# LifterPCB_v9.net
KiCad netlist of a schematic drawn in EAGLE
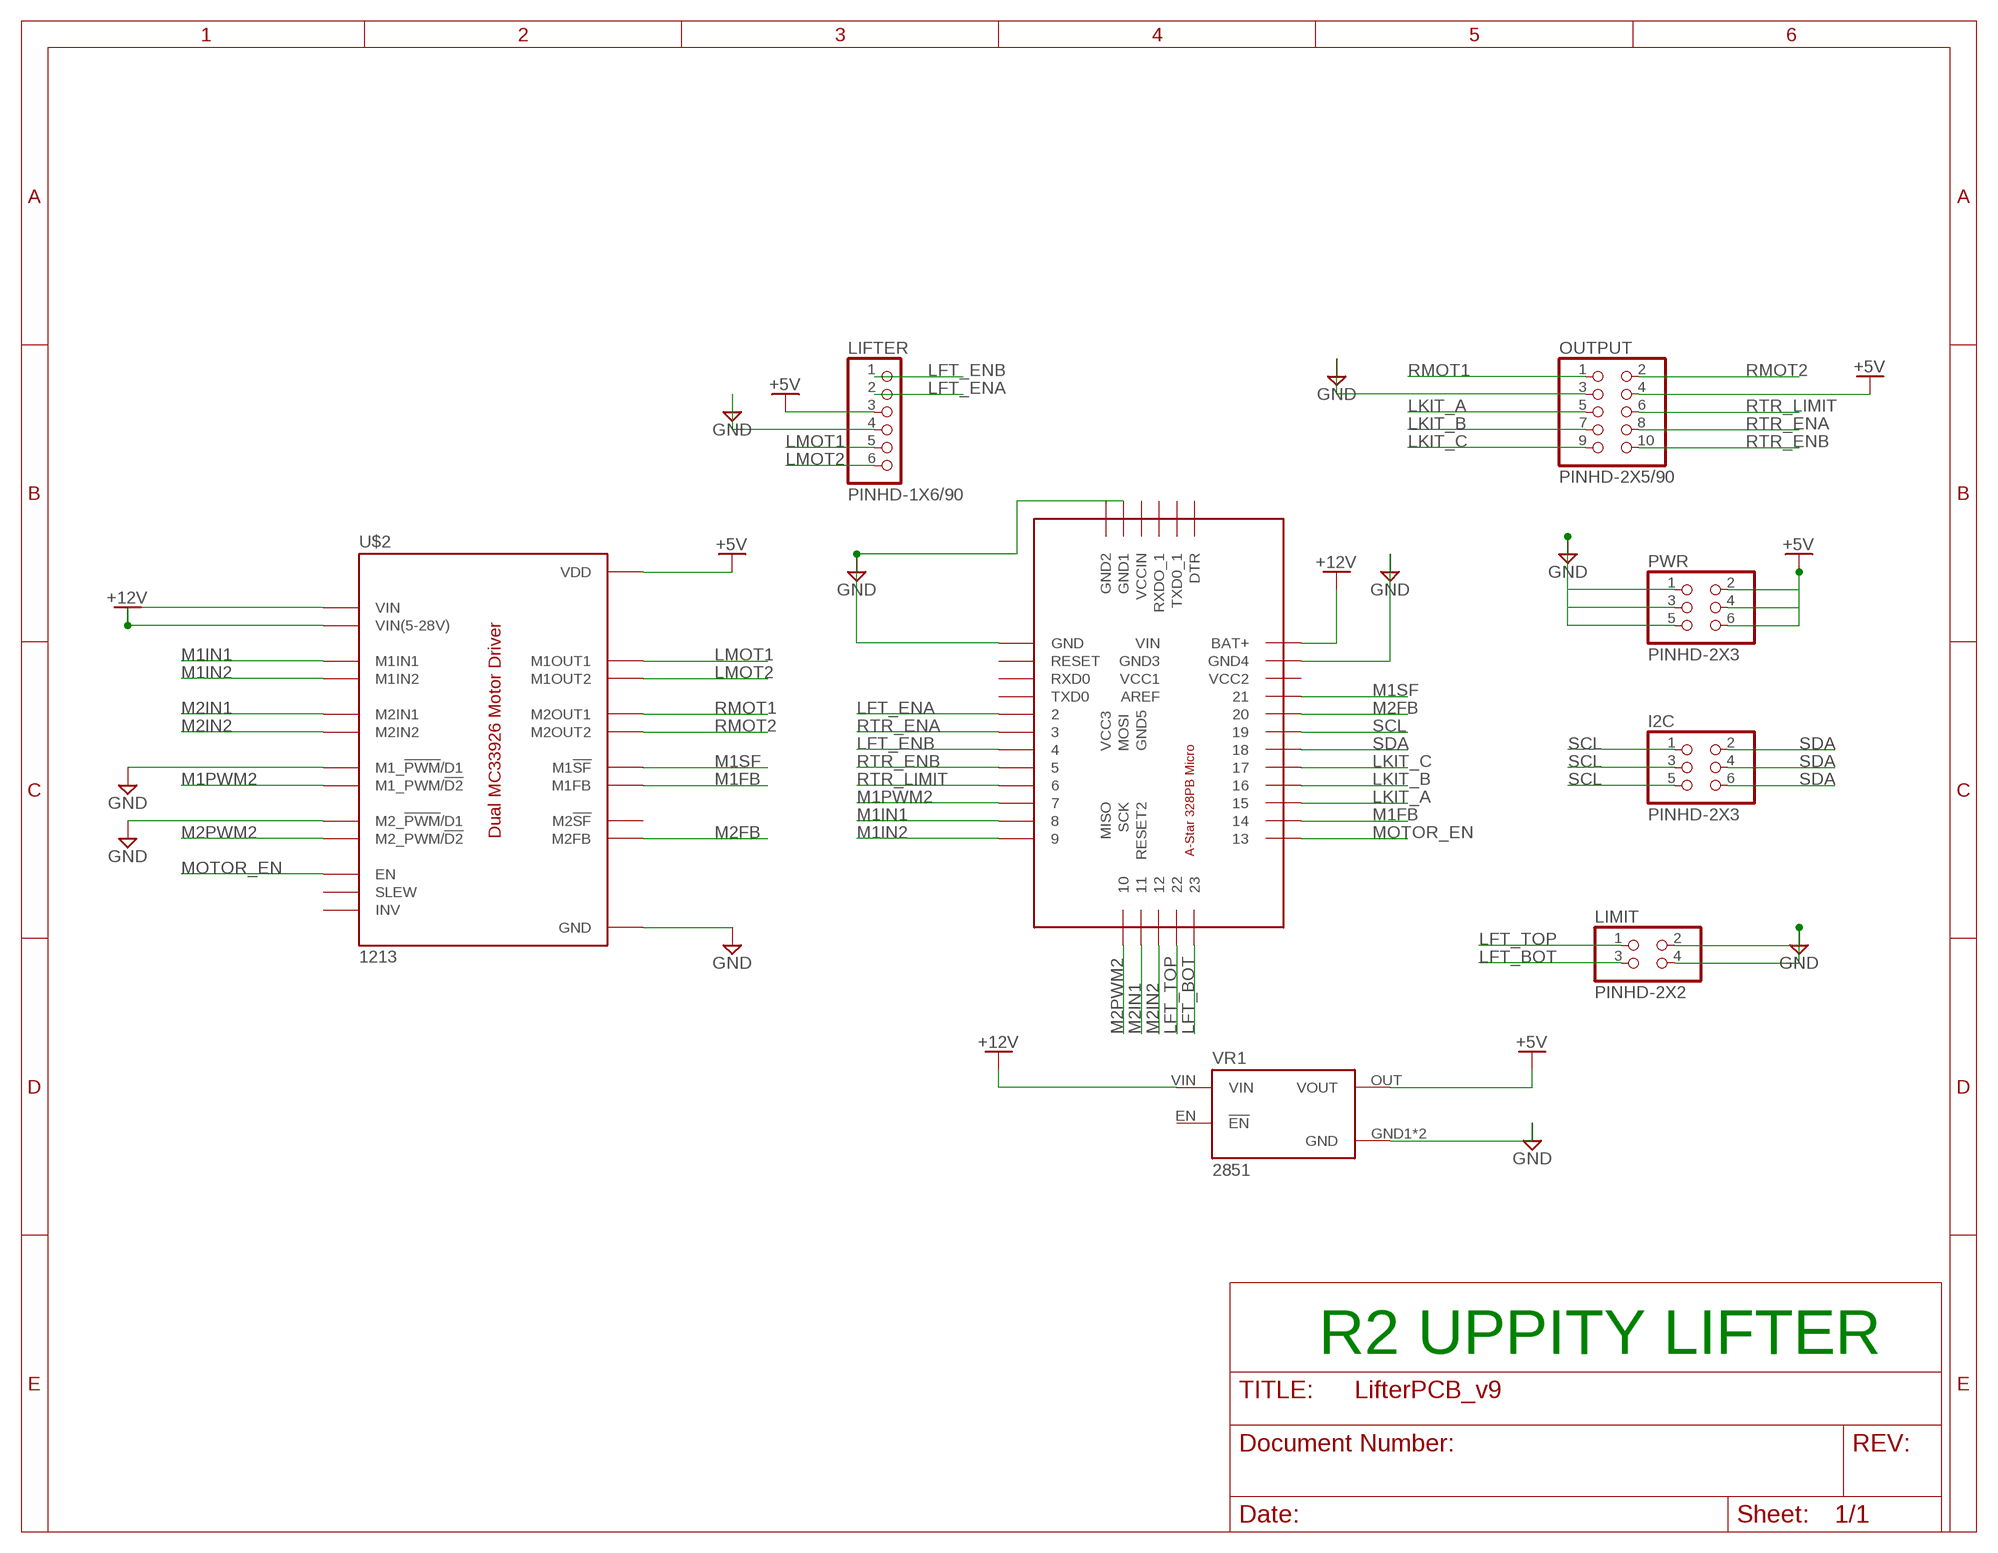
[diagram p0: schematic, sheet 1]

(export (version "E")
  (design (tool "Eeschema 10.0.6"))
  (components
    (comp (ref "I2C")
      (value "PINHD-2X3")
      (footprint "eagle-import:2X03")
      (libsource (lib "eagle-import") (part "PINHD-2X3"))
    )
    (comp (ref "LIFTER")
      (value "PINHD-1X6/90")
      (footprint "eagle-import:1X06_90")
      (libsource (lib "eagle-import") (part "PINHD-1X6/90"))
    )
    (comp (ref "LIMIT")
      (value "PINHD-2X2")
      (footprint "eagle-import:2X02")
      (libsource (lib "eagle-import") (part "PINHD-2X2"))
    )
    (comp (ref "OUTPUT")
      (value "PINHD-2X5/90")
      (footprint "eagle-import:2X05_90")
      (libsource (lib "eagle-import") (part "PINHD-2X5/90"))
    )
    (comp (ref "PWR")
      (value "PINHD-2X3")
      (footprint "eagle-import:2X03")
      (libsource (lib "eagle-import") (part "PINHD-2X3"))
    )
    (comp (ref "U$1")
      (value "POLOLU3161")
      (footprint "eagle-import:POLOLU3161")
      (libsource (lib "eagle-import") (part "POLOLU3161"))
    )
    (comp (ref "U$2")
      (value "1213")
      (footprint "eagle-import:1213")
      (libsource (lib "eagle-import") (part "1213"))
    )
    (comp (ref "VR1")
      (value "2851")
      (footprint "eagle-import:VREG_2851")
      (fields (field (name "MF") "Pololu"))
      (libsource (lib "eagle-import") (part "2851"))
    )
  )
  (nets
    (net (code "1") (name "+5V") (class "Default")
      (node (ref "LIFTER") (pin "3") (pinfunction "3_3") (pintype "passive"))
      (node (ref "OUTPUT") (pin "4") (pinfunction "4_4") (pintype "passive"))
      (node (ref "PWR") (pin "2") (pinfunction "2_2") (pintype "passive"))
      (node (ref "PWR") (pin "4") (pinfunction "4_4") (pintype "passive"))
      (node (ref "PWR") (pin "6") (pinfunction "6_6") (pintype "passive"))
      (node (ref "U$2") (pin "VDD") (pinfunction "VDD_VDD") (pintype "power_in"))
      (node (ref "U$2") (pin "VDD$1") (pinfunction "VDD_VDD$1") (pintype "power_in"))
      (node (ref "U$2") (pin "VDD$2") (pinfunction "VDD_VDD$2") (pintype "power_in"))
      (node (ref "U$2") (pin "VDD$3") (pinfunction "VDD_VDD$3") (pintype "power_in"))
      (node (ref "U$2") (pin "VDD$4") (pinfunction "VDD_VDD$4") (pintype "power_in"))
      (node (ref "U$2") (pin "VDD$5") (pinfunction "VDD_VDD$5") (pintype "power_in"))
      (node (ref "VR1") (pin "OUT") (pinfunction "VOUT_OUT") (pintype "output"))
    )
    (net (code "2") (name "+12V") (class "Default")
      (node (ref "U$1") (pin "BAT+") (pinfunction "BAT+_BAT+") (pintype "input"))
      (node (ref "U$2") (pin "MVIN") (pinfunction "VIN(5-28V)_MVIN") (pintype "input"))
      (node (ref "U$2") (pin "VIN") (pinfunction "VIN_VIN") (pintype "input"))
      (node (ref "VR1") (pin "VIN") (pinfunction "VIN_VIN") (pintype "input"))
    )
    (net (code "3") (name "/LFT_BOT") (class "Default")
      (node (ref "LIMIT") (pin "3") (pinfunction "3_3") (pintype "passive"))
      (node (ref "U$1") (pin "23") (pinfunction "23_23") (pintype "input"))
    )
    (net (code "4") (name "/LFT_ENA") (class "Default")
      (node (ref "LIFTER") (pin "2") (pinfunction "2_2") (pintype "passive"))
      (node (ref "U$1") (pin "2") (pinfunction "2_2") (pintype "input"))
    )
    (net (code "5") (name "/LFT_ENB") (class "Default")
      (node (ref "LIFTER") (pin "1") (pinfunction "1_1") (pintype "passive"))
      (node (ref "U$1") (pin "4") (pinfunction "4_4") (pintype "input"))
    )
    (net (code "6") (name "/LFT_TOP") (class "Default")
      (node (ref "LIMIT") (pin "1") (pinfunction "1_1") (pintype "passive"))
      (node (ref "U$1") (pin "22") (pinfunction "22_22") (pintype "input"))
    )
    (net (code "7") (name "/LKIT_A") (class "Default")
      (node (ref "OUTPUT") (pin "5") (pinfunction "5_5") (pintype "passive"))
      (node (ref "U$1") (pin "15") (pinfunction "15_15") (pintype "input"))
    )
    (net (code "8") (name "/LKIT_B") (class "Default")
      (node (ref "OUTPUT") (pin "7") (pinfunction "7_7") (pintype "passive"))
      (node (ref "U$1") (pin "16") (pinfunction "16_16") (pintype "input"))
    )
    (net (code "9") (name "/LKIT_C") (class "Default")
      (node (ref "OUTPUT") (pin "9") (pinfunction "9_9") (pintype "passive"))
      (node (ref "U$1") (pin "17") (pinfunction "17_17") (pintype "input"))
    )
    (net (code "10") (name "/LMOT1") (class "Default")
      (node (ref "LIFTER") (pin "5") (pinfunction "5_5") (pintype "passive"))
      (node (ref "U$2") (pin "M1OUT1") (pinfunction "M1OUT1_M1OUT1") (pintype "output"))
    )
    (net (code "11") (name "/LMOT2") (class "Default")
      (node (ref "LIFTER") (pin "6") (pinfunction "6_6") (pintype "passive"))
      (node (ref "U$2") (pin "M1OUT2") (pinfunction "M1OUT2_M1OUT2") (pintype "output"))
    )
    (net (code "12") (name "/M1FB") (class "Default")
      (node (ref "U$1") (pin "14") (pinfunction "14_14") (pintype "input"))
      (node (ref "U$2") (pin "M1FB") (pinfunction "M1FB_M1FB") (pintype "output"))
    )
    (net (code "13") (name "/M1IN1") (class "Default")
      (node (ref "U$1") (pin "8") (pinfunction "8_8") (pintype "input"))
      (node (ref "U$2") (pin "M1IN1") (pinfunction "M1IN1_M1IN1") (pintype "input"))
    )
    (net (code "14") (name "/M1IN2") (class "Default")
      (node (ref "U$1") (pin "9") (pinfunction "9_9") (pintype "input"))
      (node (ref "U$2") (pin "M1IN2") (pinfunction "M1IN2_M1IN2") (pintype "input"))
    )
    (net (code "15") (name "/M1PWM2") (class "Default")
      (node (ref "U$1") (pin "7") (pinfunction "7_7") (pintype "input"))
      (node (ref "U$2") (pin "M1PWM2") (pinfunction "M1_PWM/~{D2}_M1PWM2") (pintype "input"))
    )
    (net (code "16") (name "/M1SF") (class "Default")
      (node (ref "U$1") (pin "21") (pinfunction "21_21") (pintype "input"))
      (node (ref "U$2") (pin "M1SF") (pinfunction "M1~{SF}_M1SF") (pintype "output"))
    )
    (net (code "17") (name "/M2FB") (class "Default")
      (node (ref "U$1") (pin "20") (pinfunction "20_20") (pintype "input"))
      (node (ref "U$2") (pin "M2FB") (pinfunction "M2FB_M2FB") (pintype "output"))
    )
    (net (code "18") (name "/M2IN1") (class "Default")
      (node (ref "U$1") (pin "11$1") (pinfunction "11_11$1") (pintype "input"))
      (node (ref "U$2") (pin "M2IN1") (pinfunction "M2IN1_M2IN1") (pintype "input"))
    )
    (net (code "19") (name "/M2IN2") (class "Default")
      (node (ref "U$1") (pin "12$1") (pinfunction "12_12$1") (pintype "input"))
      (node (ref "U$2") (pin "M2IN2") (pinfunction "M2IN2_M2IN2") (pintype "input"))
    )
    (net (code "20") (name "/M2PWM2") (class "Default")
      (node (ref "U$1") (pin "10") (pinfunction "10_10") (pintype "input"))
      (node (ref "U$2") (pin "M2PWM2") (pinfunction "M2_PWM/~{D2}_M2PWM2") (pintype "input"))
    )
    (net (code "21") (name "/MOTOR_EN") (class "Default")
      (node (ref "U$1") (pin "13$1") (pinfunction "13_13$1") (pintype "input"))
      (node (ref "U$2") (pin "EN") (pinfunction "EN_EN") (pintype "input"))
    )
    (net (code "22") (name "/RMOT1") (class "Default")
      (node (ref "OUTPUT") (pin "1") (pinfunction "1_1") (pintype "passive"))
      (node (ref "U$2") (pin "M2OUT1") (pinfunction "M2OUT1_M2OUT1") (pintype "output"))
    )
    (net (code "23") (name "/RMOT2") (class "Default")
      (node (ref "OUTPUT") (pin "2") (pinfunction "2_2") (pintype "passive"))
      (node (ref "U$2") (pin "M2OUT2") (pinfunction "M2OUT2_M2OUT2") (pintype "output"))
    )
    (net (code "24") (name "/RTR_ENA") (class "Default")
      (node (ref "OUTPUT") (pin "8") (pinfunction "8_8") (pintype "passive"))
      (node (ref "U$1") (pin "3") (pinfunction "3_3") (pintype "input"))
    )
    (net (code "25") (name "/RTR_ENB") (class "Default")
      (node (ref "OUTPUT") (pin "10") (pinfunction "10_10") (pintype "passive"))
      (node (ref "U$1") (pin "5") (pinfunction "5_5") (pintype "input"))
    )
    (net (code "26") (name "/RTR_LIMIT") (class "Default")
      (node (ref "OUTPUT") (pin "6") (pinfunction "6_6") (pintype "passive"))
      (node (ref "U$1") (pin "6") (pinfunction "6_6") (pintype "input"))
    )
    (net (code "27") (name "/SCL") (class "Default")
      (node (ref "I2C") (pin "1") (pinfunction "1_1") (pintype "passive"))
      (node (ref "I2C") (pin "3") (pinfunction "3_3") (pintype "passive"))
      (node (ref "I2C") (pin "5") (pinfunction "5_5") (pintype "passive"))
      (node (ref "U$1") (pin "19") (pinfunction "19_19") (pintype "input"))
    )
    (net (code "28") (name "/SDA") (class "Default")
      (node (ref "I2C") (pin "2") (pinfunction "2_2") (pintype "passive"))
      (node (ref "I2C") (pin "4") (pinfunction "4_4") (pintype "passive"))
      (node (ref "I2C") (pin "6") (pinfunction "6_6") (pintype "passive"))
      (node (ref "U$1") (pin "18") (pinfunction "18_18") (pintype "input"))
    )
    (net (code "29") (name "GND") (class "Default")
      (node (ref "LIFTER") (pin "4") (pinfunction "4_4") (pintype "passive"))
      (node (ref "LIMIT") (pin "2") (pinfunction "2_2") (pintype "passive"))
      (node (ref "LIMIT") (pin "4") (pinfunction "4_4") (pintype "passive"))
      (node (ref "OUTPUT") (pin "3") (pinfunction "3_3") (pintype "passive"))
      (node (ref "PWR") (pin "1") (pinfunction "1_1") (pintype "passive"))
      (node (ref "PWR") (pin "3") (pinfunction "3_3") (pintype "passive"))
      (node (ref "PWR") (pin "5") (pinfunction "5_5") (pintype "passive"))
      (node (ref "U$1") (pin "GND2") (pinfunction "GND4_GND2") (pintype "input"))
      (node (ref "U$1") (pin "GND4") (pinfunction "GND2_GND4") (pintype "input"))
      (node (ref "U$1") (pin "GND5") (pinfunction "GND1_GND5") (pintype "input"))
      (node (ref "U$1") (pin "GND6") (pinfunction "GND_GND6") (pintype "input"))
      (node (ref "U$2") (pin "GND") (pinfunction "GND_GND") (pintype "power_in"))
      (node (ref "U$2") (pin "GND$1") (pinfunction "GND_GND$1") (pintype "power_in"))
      (node (ref "U$2") (pin "GND$2") (pinfunction "GND_GND$2") (pintype "power_in"))
      (node (ref "U$2") (pin "M1PWM1") (pinfunction "M1_~{PWM}/D1_M1PWM1") (pintype "input"))
      (node (ref "U$2") (pin "M2PWM1") (pinfunction "M2_~{PWM}/D1_M2PWM1") (pintype "input"))
      (node (ref "U$2") (pin "MGND") (pinfunction "GND_MGND") (pintype "power_in"))
      (node (ref "VR1") (pin "GND1") (pinfunction "GND_GND1") (pintype "power_in"))
      (node (ref "VR1") (pin "GND2") (pinfunction "GND_GND2") (pintype "power_in"))
    )
    (net (code "30") (name "unconnected-(U$1-GND5-PadGND1)") (class "Default")
      (node (ref "U$1") (pin "GND1") (pinfunction "GND5_GND1") (pintype "input"))
    )
    (net (code "31") (name "unconnected-(U$1-MISO-Pad12$2)") (class "Default")
      (node (ref "U$1") (pin "12$2") (pinfunction "MISO_12$2") (pintype "input"))
    )
    (net (code "32") (name "unconnected-(U$1-MOSI-Pad11$2)") (class "Default")
      (node (ref "U$1") (pin "11$2") (pinfunction "MOSI_11$2") (pintype "input"))
    )
    (net (code "33") (name "unconnected-(U$1-PadAREF)") (class "Default")
      (node (ref "U$1") (pin "AREF") (pinfunction "AREF_AREF") (pintype "input"))
    )
    (net (code "34") (name "unconnected-(U$1-PadDTR)") (class "Default")
      (node (ref "U$1") (pin "DTR") (pinfunction "DTR_DTR") (pintype "input"))
    )
    (net (code "35") (name "unconnected-(U$1-PadGND3)") (class "Default")
      (node (ref "U$1") (pin "GND3") (pinfunction "GND3_GND3") (pintype "input"))
    )
    (net (code "36") (name "unconnected-(U$1-PadVCC1)") (class "Default")
      (node (ref "U$1") (pin "VCC1") (pinfunction "VCC1_VCC1") (pintype "input"))
    )
    (net (code "37") (name "unconnected-(U$1-PadVCC2)") (class "Default")
      (node (ref "U$1") (pin "VCC2") (pinfunction "VCC2_VCC2") (pintype "input"))
    )
    (net (code "38") (name "unconnected-(U$1-PadVCC3)") (class "Default")
      (node (ref "U$1") (pin "VCC3") (pinfunction "VCC3_VCC3") (pintype "input"))
    )
    (net (code "39") (name "unconnected-(U$1-PadVCCIN)") (class "Default")
      (node (ref "U$1") (pin "VCCIN") (pinfunction "VCCIN_VCCIN") (pintype "input"))
    )
    (net (code "40") (name "unconnected-(U$1-PadVIN)") (class "Default")
      (node (ref "U$1") (pin "VIN") (pinfunction "VIN_VIN") (pintype "input"))
    )
    (net (code "41") (name "unconnected-(U$1-RESET-PadRESET2)") (class "Default")
      (node (ref "U$1") (pin "RESET2") (pinfunction "RESET_RESET2") (pintype "input"))
    )
    (net (code "42") (name "unconnected-(U$1-RESET2-PadRESET1)") (class "Default")
      (node (ref "U$1") (pin "RESET1") (pinfunction "RESET2_RESET1") (pintype "input"))
    )
    (net (code "43") (name "unconnected-(U$1-RXD0-PadRXD0_1)") (class "Default")
      (node (ref "U$1") (pin "RXD0_1") (pinfunction "RXD0_RXD0_1") (pintype "input"))
    )
    (net (code "44") (name "unconnected-(U$1-RXDO_1-PadRXD0_2)") (class "Default")
      (node (ref "U$1") (pin "RXD0_2") (pinfunction "RXDO_1_RXD0_2") (pintype "input"))
    )
    (net (code "45") (name "unconnected-(U$1-SCK-Pad13$2)") (class "Default")
      (node (ref "U$1") (pin "13$2") (pinfunction "SCK_13$2") (pintype "input"))
    )
    (net (code "46") (name "unconnected-(U$1-TXD0-PadTXD0_1)") (class "Default")
      (node (ref "U$1") (pin "TXD0_1") (pinfunction "TXD0_TXD0_1") (pintype "input"))
    )
    (net (code "47") (name "unconnected-(U$1-TXD0_1-PadTXD0_2)") (class "Default")
      (node (ref "U$1") (pin "TXD0_2") (pinfunction "TXD0_1_TXD0_2") (pintype "input"))
    )
    (net (code "48") (name "unconnected-(U$2-M2~{SF}-PadM2SF)") (class "Default")
      (node (ref "U$2") (pin "M2SF") (pinfunction "M2~{SF}_M2SF") (pintype "output"))
    )
    (net (code "49") (name "unconnected-(U$2-PadINV)") (class "Default")
      (node (ref "U$2") (pin "INV") (pinfunction "INV_INV") (pintype "input"))
    )
    (net (code "50") (name "unconnected-(U$2-PadSLEW)") (class "Default")
      (node (ref "U$2") (pin "SLEW") (pinfunction "SLEW_SLEW") (pintype "input"))
    )
    (net (code "51") (name "unconnected-(VR1-~{EN}-PadEN)") (class "Default")
      (node (ref "VR1") (pin "EN") (pinfunction "~{EN}_EN") (pintype "input"))
    )
  )
)
